# Dynamixel_Power.net
KiCad netlist of a schematic drawn in Altium Designer
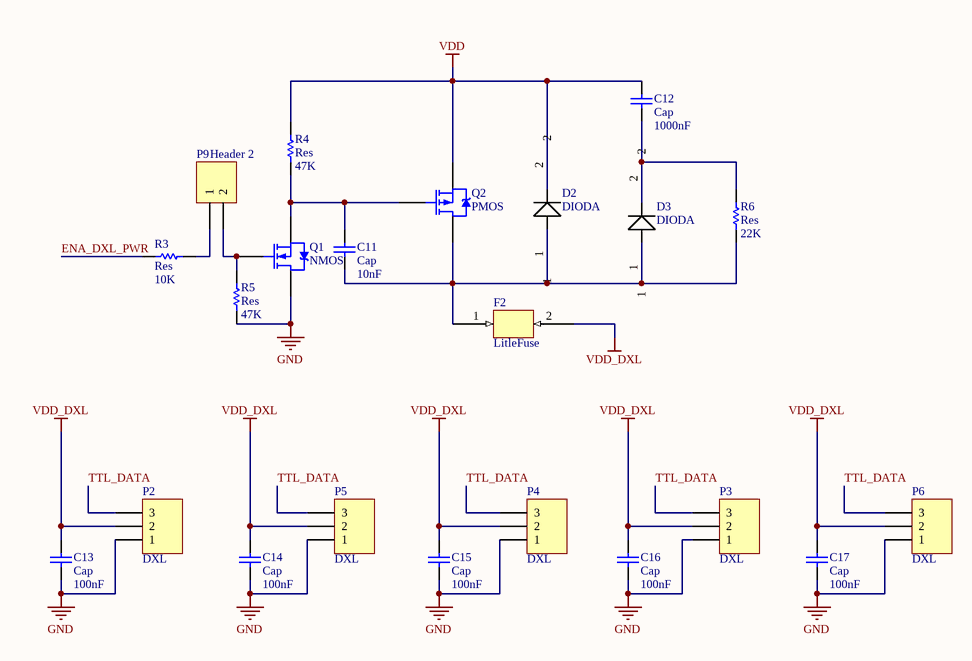
[diagram p0: Dynamixel Power.SchDoc]

(export (version "E")
  (design (tool "Eeschema 10.0.6"))
  (components
    (comp (ref "C11")
      (value "Cap")
      (footprint "0603-CAP")
      (description "Capacitor")
      (fields (field (name "ALTIUM_VALUE") "10nF") (field (name "PUBLISHER") "Altium Limited"))
      (libsource (lib "BarelangRobotics") (part "Cap"))
    )
    (comp (ref "C12")
      (value "Cap")
      (footprint "0603-CAP")
      (description "Capacitor")
      (fields (field (name "ALTIUM_VALUE") "1000nF") (field (name "PUBLISHER") "Altium Limited"))
      (libsource (lib "BarelangRobotics") (part "Cap"))
    )
    (comp (ref "C13")
      (value "Cap")
      (footprint "0603-CAP")
      (description "Capacitor")
      (fields (field (name "ALTIUM_VALUE") "100nF") (field (name "PUBLISHER") "Altium Limited"))
      (libsource (lib "BarelangRobotics") (part "Cap"))
    )
    (comp (ref "C14")
      (value "Cap")
      (footprint "0603-CAP")
      (description "Capacitor")
      (fields (field (name "ALTIUM_VALUE") "100nF") (field (name "PUBLISHER") "Altium Limited"))
      (libsource (lib "BarelangRobotics") (part "Cap"))
    )
    (comp (ref "C15")
      (value "Cap")
      (footprint "0603-CAP")
      (description "Capacitor")
      (fields (field (name "ALTIUM_VALUE") "100nF") (field (name "PUBLISHER") "Altium Limited"))
      (libsource (lib "BarelangRobotics") (part "Cap"))
    )
    (comp (ref "C16")
      (value "Cap")
      (footprint "0603-CAP")
      (description "Capacitor")
      (fields (field (name "ALTIUM_VALUE") "100nF") (field (name "PUBLISHER") "Altium Limited"))
      (libsource (lib "BarelangRobotics") (part "Cap"))
    )
    (comp (ref "C17")
      (value "Cap")
      (footprint "0603-CAP")
      (description "Capacitor")
      (fields (field (name "ALTIUM_VALUE") "100nF") (field (name "PUBLISHER") "Altium Limited"))
      (libsource (lib "BarelangRobotics") (part "Cap"))
    )
    (comp (ref "D2")
      (value "DIODA")
      (footprint "DIODE SS14 SODFL")
      (libsource (lib "BRCM-Additional-Library") (part "DIODA"))
    )
    (comp (ref "D3")
      (value "DIODA")
      (footprint "DIODE SS14 SODFL")
      (libsource (lib "BRCM-Additional-Library") (part "DIODA"))
    )
    (comp (ref "F2")
      (value "LitleFuse")
      (footprint "LitleFuse")
      (libsource (lib "BRCM-Additional-Library") (part "LitleFuse"))
    )
    (comp (ref "P2") (value "DXL") (footprint "DXL") (libsource (lib "BarelangRobotics") (part "DXL")))
    (comp (ref "P3") (value "DXL") (footprint "DXL") (libsource (lib "BarelangRobotics") (part "DXL")))
    (comp (ref "P4") (value "DXL") (footprint "DXL") (libsource (lib "BarelangRobotics") (part "DXL")))
    (comp (ref "P5") (value "DXL") (footprint "DXL") (libsource (lib "BarelangRobotics") (part "DXL")))
    (comp (ref "P6") (value "DXL") (footprint "DXL") (libsource (lib "BarelangRobotics") (part "DXL")))
    (comp (ref "P9")
      (value "Header 2")
      (footprint "HDR1X2")
      (description "Header, 2-Pin")
      (fields (field (name "PUBLISHER") "Altium Limited"))
      (libsource (lib "BarelangRobotics") (part "Header 2"))
    )
    (comp (ref "Q1")
      (value "NMOS")
      (footprint "SOT23")
      (description "N-Channel Power MOSFET")
      (fields (field (name "PUBLISHER") "Altium Limited"))
      (libsource (lib "BarelangRobotics") (part "NMOS"))
    )
    (comp (ref "Q2")
      (value "PMOS")
      (footprint "TO263")
      (description "P-Channel Power MOSFET")
      (fields (field (name "PUBLISHER") "Altium Limited"))
      (libsource (lib "BarelangRobotics") (part "PMOS"))
    )
    (comp (ref "R3")
      (value "Res")
      (footprint "0603-RES")
      (description "Resistor")
      (fields (field (name "ALTIUM_VALUE") "10K") (field (name "PUBLISHER") "Altium Limited"))
      (libsource (lib "BarelangRobotics") (part "Res"))
    )
    (comp (ref "R4")
      (value "Res")
      (footprint "0603-RES")
      (description "Resistor")
      (fields (field (name "ALTIUM_VALUE") "47K") (field (name "PUBLISHER") "Altium Limited"))
      (libsource (lib "BarelangRobotics") (part "Res"))
    )
    (comp (ref "R5")
      (value "Res")
      (footprint "0603-RES")
      (description "Resistor")
      (fields (field (name "ALTIUM_VALUE") "47K") (field (name "PUBLISHER") "Altium Limited"))
      (libsource (lib "BarelangRobotics") (part "Res"))
    )
    (comp (ref "R6")
      (value "Res")
      (footprint "0603-RES")
      (description "Resistor")
      (fields (field (name "ALTIUM_VALUE") "22K") (field (name "PUBLISHER") "Altium Limited"))
      (libsource (lib "BarelangRobotics") (part "Res"))
    )
  )
  (nets
    (net (code "1") (name "/ENA_DXL_PWR") (class "Default")
      (node (ref "R3") (pin "1") (pinfunction "1_1") (pintype "passive"))
    )
    (net (code "2") (name "/TTL_DATA") (class "Default")
      (node (ref "P2") (pin "3") (pinfunction "3_3") (pintype "passive"))
      (node (ref "P3") (pin "3") (pinfunction "3_3") (pintype "passive"))
      (node (ref "P4") (pin "3") (pinfunction "3_3") (pintype "passive"))
      (node (ref "P5") (pin "3") (pinfunction "3_3") (pintype "passive"))
      (node (ref "P6") (pin "3") (pinfunction "3_3") (pintype "passive"))
    )
    (net (code "3") (name "GND") (class "Default")
      (node (ref "C13") (pin "1") (pinfunction "1_1") (pintype "passive"))
      (node (ref "C14") (pin "1") (pinfunction "1_1") (pintype "passive"))
      (node (ref "C15") (pin "1") (pinfunction "1_1") (pintype "passive"))
      (node (ref "C16") (pin "1") (pinfunction "1_1") (pintype "passive"))
      (node (ref "C17") (pin "1") (pinfunction "1_1") (pintype "passive"))
      (node (ref "P2") (pin "1") (pinfunction "1_1") (pintype "passive"))
      (node (ref "P3") (pin "1") (pinfunction "1_1") (pintype "passive"))
      (node (ref "P4") (pin "1") (pinfunction "1_1") (pintype "passive"))
      (node (ref "P5") (pin "1") (pinfunction "1_1") (pintype "passive"))
      (node (ref "P6") (pin "1") (pinfunction "1_1") (pintype "passive"))
      (node (ref "Q1") (pin "3") (pinfunction "D_3") (pintype "passive"))
      (node (ref "R5") (pin "1") (pinfunction "1_1") (pintype "passive"))
    )
    (net (code "4") (name "Net-(C12-Pad1)") (class "Default")
      (node (ref "C12") (pin "1") (pinfunction "1_1") (pintype "passive"))
      (node (ref "D3") (pin "2") (pinfunction "2_2") (pintype "passive"))
      (node (ref "R6") (pin "2") (pinfunction "2_2") (pintype "passive"))
    )
    (net (code "5") (name "Net-(P9-Pad1)") (class "Default")
      (node (ref "P9") (pin "1") (pinfunction "1_1") (pintype "passive"))
      (node (ref "R3") (pin "2") (pinfunction "2_2") (pintype "passive"))
    )
    (net (code "6") (name "Net-(Q1-G)") (class "Default")
      (node (ref "P9") (pin "2") (pinfunction "2_2") (pintype "passive"))
      (node (ref "Q1") (pin "1") (pinfunction "G_1") (pintype "passive"))
      (node (ref "R5") (pin "2") (pinfunction "2_2") (pintype "passive"))
    )
    (net (code "7") (name "Net-(Q1-S)") (class "Default")
      (node (ref "C11") (pin "2") (pinfunction "2_2") (pintype "passive"))
      (node (ref "Q1") (pin "2") (pinfunction "S_2") (pintype "passive"))
      (node (ref "Q2") (pin "1") (pinfunction "G_1") (pintype "passive"))
      (node (ref "R4") (pin "1") (pinfunction "1_1") (pintype "passive"))
    )
    (net (code "8") (name "Net-(Q2-D)") (class "Default")
      (node (ref "C11") (pin "1") (pinfunction "1_1") (pintype "passive"))
      (node (ref "D2") (pin "1") (pinfunction "1_1") (pintype "passive"))
      (node (ref "D3") (pin "1") (pinfunction "1_1") (pintype "passive"))
      (node (ref "F2") (pin "1") (pintype "input"))
      (node (ref "Q2") (pin "3") (pinfunction "D_3") (pintype "passive"))
      (node (ref "R6") (pin "1") (pinfunction "1_1") (pintype "passive"))
    )
    (net (code "9") (name "VDD") (class "Default")
      (node (ref "C12") (pin "2") (pinfunction "2_2") (pintype "passive"))
      (node (ref "D2") (pin "2") (pinfunction "2_2") (pintype "passive"))
      (node (ref "Q2") (pin "2") (pinfunction "S_2") (pintype "passive"))
      (node (ref "R4") (pin "2") (pinfunction "2_2") (pintype "passive"))
    )
    (net (code "10") (name "VDD_DXL") (class "Default")
      (node (ref "C13") (pin "2") (pinfunction "2_2") (pintype "passive"))
      (node (ref "C14") (pin "2") (pinfunction "2_2") (pintype "passive"))
      (node (ref "C15") (pin "2") (pinfunction "2_2") (pintype "passive"))
      (node (ref "C16") (pin "2") (pinfunction "2_2") (pintype "passive"))
      (node (ref "C17") (pin "2") (pinfunction "2_2") (pintype "passive"))
      (node (ref "F2") (pin "2") (pintype "input"))
      (node (ref "P2") (pin "2") (pinfunction "2_2") (pintype "passive"))
      (node (ref "P3") (pin "2") (pinfunction "2_2") (pintype "passive"))
      (node (ref "P4") (pin "2") (pinfunction "2_2") (pintype "passive"))
      (node (ref "P5") (pin "2") (pinfunction "2_2") (pintype "passive"))
      (node (ref "P6") (pin "2") (pinfunction "2_2") (pintype "passive"))
    )
  )
)
